# Sheet2.net
KiCad netlist of a schematic drawn in Altium Designer
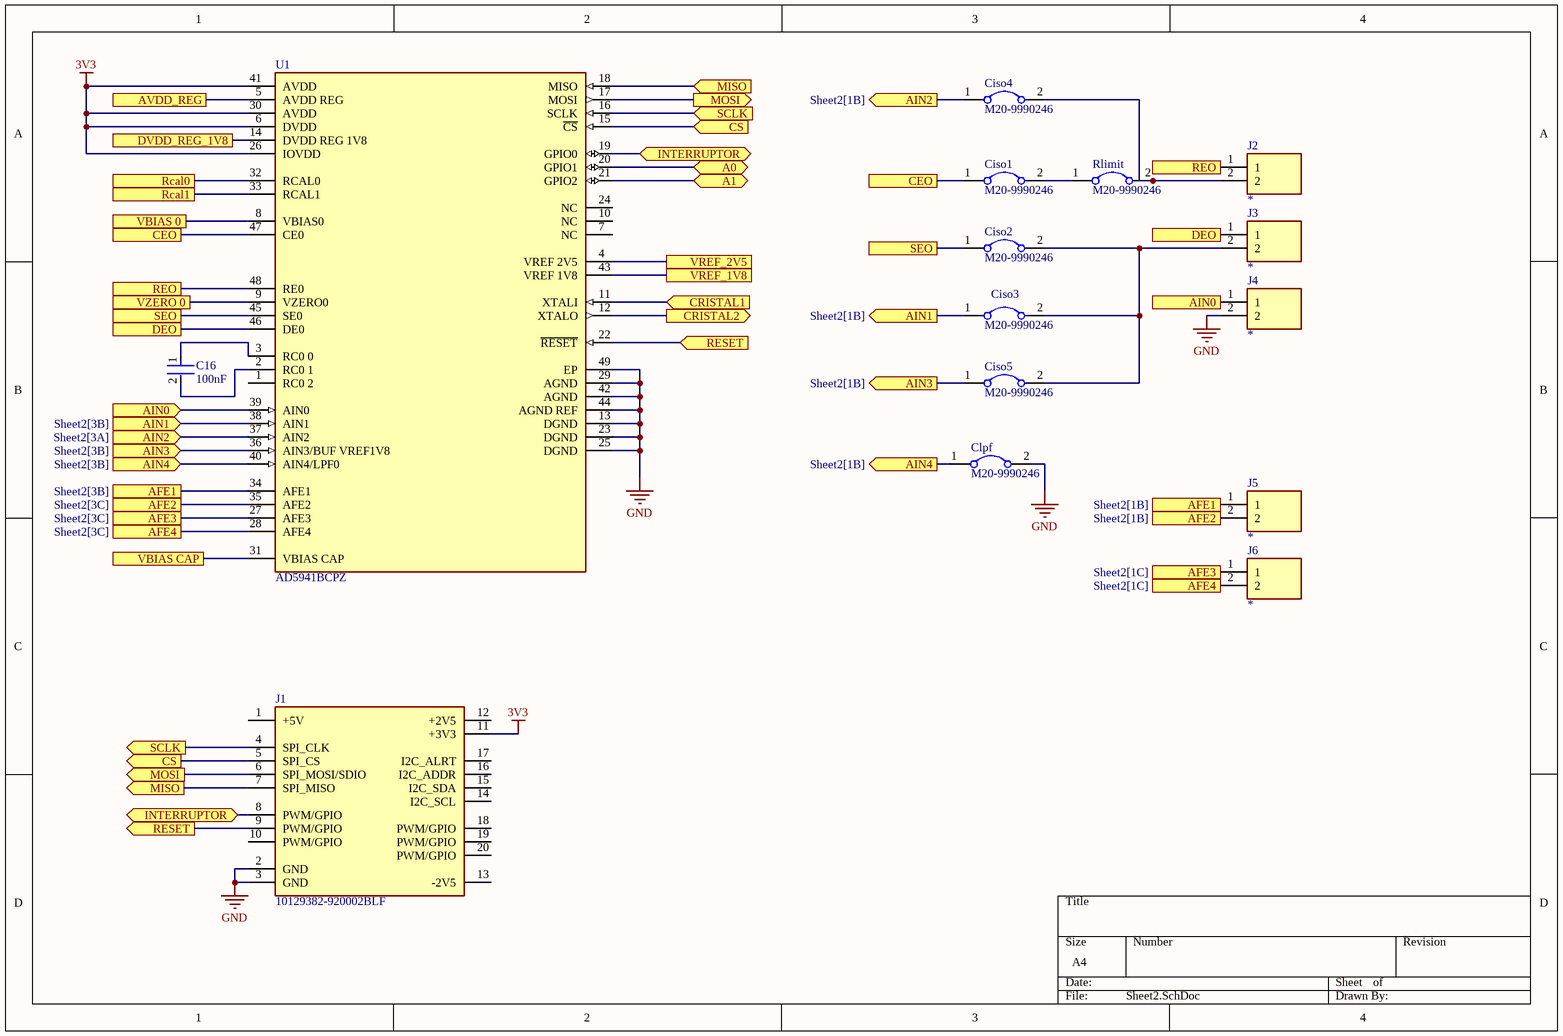
[diagram p0: Sheet2.SchDoc]

(export (version "E")
  (design (tool "Eeschema 10.0.6"))
  (components
    (comp (ref "C16")
      (value "100nF")
      (footprint "FP-GRM18-0_15-MFG")
      (description "CAP CER 10UF 10V X5R 0603")
      (fields
        (field (name "OCTOPART") "https://octopart.com/grm188r61a106ke69d-murata-22851381")
        (field (name "MANUFACTURER PART NUMBER") "GRM188R61A106KE69D")
      )
      (libsource (lib "Altium Content Vault") (part "11868f565c42a9108669ba33697ecf6"))
    )
    (comp (ref "Ciso1")
      (value "M20-9990246")
      (footprint "Male Header Socket 2-position")
      (description "Headers & Wire Housings M20 2 Position SIL VERTICAL PTH HEADER TIN")
      (libsource (lib "CEDRA_Connectors") (part "M20-9990246 (JUMPER)"))
    )
    (comp (ref "Ciso2")
      (value "M20-9990246")
      (footprint "Male Header Socket 2-position")
      (description "Headers & Wire Housings M20 2 Position SIL VERTICAL PTH HEADER TIN")
      (libsource (lib "CEDRA_Connectors") (part "M20-9990246 (JUMPER)"))
    )
    (comp (ref "Ciso3")
      (value "M20-9990246")
      (footprint "Male Header Socket 2-position")
      (description "Headers & Wire Housings M20 2 Position SIL VERTICAL PTH HEADER TIN")
      (libsource (lib "CEDRA_Connectors") (part "M20-9990246 (JUMPER)"))
    )
    (comp (ref "Ciso4")
      (value "M20-9990246")
      (footprint "Male Header Socket 2-position")
      (description "Headers & Wire Housings M20 2 Position SIL VERTICAL PTH HEADER TIN")
      (libsource (lib "CEDRA_Connectors") (part "M20-9990246 (JUMPER)"))
    )
    (comp (ref "Ciso5")
      (value "M20-9990246")
      (footprint "Male Header Socket 2-position")
      (description "Headers & Wire Housings M20 2 Position SIL VERTICAL PTH HEADER TIN")
      (libsource (lib "CEDRA_Connectors") (part "M20-9990246 (JUMPER)"))
    )
    (comp (ref "Clpf")
      (value "M20-9990246")
      (footprint "Male Header Socket 2-position")
      (description "Headers & Wire Housings M20 2 Position SIL VERTICAL PTH HEADER TIN")
      (libsource (lib "CEDRA_Connectors") (part "M20-9990246 (JUMPER)"))
    )
    (comp (ref "J1")
      (value "10129382-920002BLF")
      (footprint "Base Board Modular Connector (MALE)")
      (libsource (lib "CEDRA_Connectors") (part "Base Board Modular Connector (MALE)"))
    )
    (comp (ref "J2")
      (value "~")
      (footprint "Terminal Block 2-position")
      (fields (field (name "PARAMETER 1") "*"))
      (libsource (lib "CEDRA_Connectors") (part "TB0011-350-02BE"))
    )
    (comp (ref "J3")
      (value "~")
      (footprint "Terminal Block 2-position")
      (fields (field (name "PARAMETER 1") "*"))
      (libsource (lib "CEDRA_Connectors") (part "TB0011-350-02BE"))
    )
    (comp (ref "J4")
      (value "~")
      (footprint "Terminal Block 2-position")
      (fields (field (name "PARAMETER 1") "*"))
      (libsource (lib "CEDRA_Connectors") (part "TB0011-350-02BE"))
    )
    (comp (ref "J5")
      (value "~")
      (footprint "Terminal Block 2-position")
      (fields (field (name "PARAMETER 1") "*"))
      (libsource (lib "CEDRA_Connectors") (part "TB0011-350-02BE"))
    )
    (comp (ref "J6")
      (value "~")
      (footprint "Terminal Block 2-position")
      (fields (field (name "PARAMETER 1") "*"))
      (libsource (lib "CEDRA_Connectors") (part "TB0011-350-02BE"))
    )
    (comp (ref "Rlimit")
      (value "M20-9990246")
      (footprint "Male Header Socket 2-position")
      (description "Headers & Wire Housings M20 2 Position SIL VERTICAL PTH HEADER TIN")
      (libsource (lib "CEDRA_Connectors") (part "M20-9990246 (JUMPER)"))
    )
    (comp (ref "U1")
      (value "AD5941BCPZ")
      (footprint "FP-CP-48-4-IPC_A")
      (description "BIO-IMPEDANCE & ELECTROCHEMICAL")
      (libsource (lib "Altium Content Vault") (part "6a54f8959a82146fbd7e10af4c03d01"))
    )
  )
  (nets
    (net (code "1") (name "/A0") (class "Default")
      (node (ref "U1") (pin "20") (pinfunction "GPIO1_20") (pintype "bidirectional"))
    )
    (net (code "2") (name "/A1") (class "Default")
      (node (ref "U1") (pin "21") (pinfunction "GPIO2_21") (pintype "bidirectional"))
    )
    (net (code "3") (name "/AFE1") (class "Default")
      (node (ref "J5") (pin "1") (pinfunction "1_1") (pintype "passive"))
      (node (ref "U1") (pin "34") (pinfunction "AFE1_34") (pintype "passive"))
    )
    (net (code "4") (name "/AFE2") (class "Default")
      (node (ref "J5") (pin "2") (pinfunction "2_2") (pintype "passive"))
      (node (ref "U1") (pin "35") (pinfunction "AFE2_35") (pintype "passive"))
    )
    (net (code "5") (name "/AFE3") (class "Default")
      (node (ref "J6") (pin "1") (pinfunction "1_1") (pintype "passive"))
      (node (ref "U1") (pin "27") (pinfunction "AFE3_27") (pintype "passive"))
    )
    (net (code "6") (name "/AFE4") (class "Default")
      (node (ref "J6") (pin "2") (pinfunction "2_2") (pintype "passive"))
      (node (ref "U1") (pin "28") (pinfunction "AFE4_28") (pintype "passive"))
    )
    (net (code "7") (name "/AIN0") (class "Default")
      (node (ref "J4") (pin "1") (pinfunction "1_1") (pintype "passive"))
      (node (ref "U1") (pin "39") (pinfunction "AIN0_39") (pintype "input"))
    )
    (net (code "8") (name "/AIN1") (class "Default")
      (node (ref "Ciso3") (pin "1") (pinfunction "1_1") (pintype "passive"))
      (node (ref "U1") (pin "38") (pinfunction "AIN1_38") (pintype "input"))
    )
    (net (code "9") (name "/AIN2") (class "Default")
      (node (ref "Ciso4") (pin "1") (pinfunction "1_1") (pintype "passive"))
      (node (ref "U1") (pin "37") (pinfunction "AIN2_37") (pintype "input"))
    )
    (net (code "10") (name "/AIN3") (class "Default")
      (node (ref "Ciso5") (pin "1") (pinfunction "1_1") (pintype "passive"))
      (node (ref "U1") (pin "36") (pinfunction "AIN3/BUF_VREF1V8_36") (pintype "input"))
    )
    (net (code "11") (name "/AIN4") (class "Default")
      (node (ref "Clpf") (pin "1") (pinfunction "1_1") (pintype "passive"))
      (node (ref "U1") (pin "40") (pinfunction "AIN4/LPF0_40") (pintype "input"))
    )
    (net (code "12") (name "/AVDD_REG") (class "Default")
      (node (ref "U1") (pin "5") (pinfunction "AVDD_REG_5") (pintype "power_in"))
    )
    (net (code "13") (name "/CEO") (class "Default")
      (node (ref "Ciso1") (pin "1") (pinfunction "1_1") (pintype "passive"))
      (node (ref "U1") (pin "47") (pinfunction "CE0_47") (pintype "passive"))
    )
    (net (code "14") (name "/CRISTAL1") (class "Default")
      (node (ref "U1") (pin "11") (pinfunction "XTALI_11") (pintype "input"))
    )
    (net (code "15") (name "/CRISTAL2") (class "Default")
      (node (ref "U1") (pin "12") (pinfunction "XTALO_12") (pintype "output"))
    )
    (net (code "16") (name "/CS") (class "Default")
      (node (ref "J1") (pin "5") (pinfunction "SPI_CS_5") (pintype "passive"))
      (node (ref "U1") (pin "15") (pinfunction "~{CS}_15") (pintype "input"))
    )
    (net (code "17") (name "/DEO") (class "Default")
      (node (ref "J3") (pin "1") (pinfunction "1_1") (pintype "passive"))
      (node (ref "U1") (pin "46") (pinfunction "DE0_46") (pintype "passive"))
    )
    (net (code "18") (name "/DVDD_REG_1V8") (class "Default")
      (node (ref "U1") (pin "14") (pinfunction "DVDD_REG_1V8_14") (pintype "power_in"))
    )
    (net (code "19") (name "/INTERRUPTOR") (class "Default")
      (node (ref "J1") (pin "8") (pinfunction "PWM/GPIO_8") (pintype "passive"))
      (node (ref "U1") (pin "19") (pinfunction "GPIO0_19") (pintype "bidirectional"))
    )
    (net (code "20") (name "/MISO") (class "Default")
      (node (ref "J1") (pin "7") (pinfunction "SPI_MISO_7") (pintype "passive"))
      (node (ref "U1") (pin "18") (pinfunction "MISO_18") (pintype "input"))
    )
    (net (code "21") (name "/MOSI") (class "Default")
      (node (ref "J1") (pin "6") (pinfunction "SPI_MOSI/SDIO_6") (pintype "passive"))
      (node (ref "U1") (pin "17") (pinfunction "MOSI_17") (pintype "output"))
    )
    (net (code "22") (name "/REO") (class "Default")
      (node (ref "J2") (pin "1") (pinfunction "1_1") (pintype "passive"))
      (node (ref "U1") (pin "48") (pinfunction "RE0_48") (pintype "passive"))
    )
    (net (code "23") (name "/RESET") (class "Default")
      (node (ref "J1") (pin "9") (pinfunction "PWM/GPIO_9") (pintype "passive"))
      (node (ref "U1") (pin "22") (pinfunction "~{RESET}_22") (pintype "input"))
    )
    (net (code "24") (name "/Rcal0") (class "Default")
      (node (ref "U1") (pin "32") (pinfunction "RCAL0_32") (pintype "passive"))
    )
    (net (code "25") (name "/Rcal1") (class "Default")
      (node (ref "U1") (pin "33") (pinfunction "RCAL1_33") (pintype "passive"))
    )
    (net (code "26") (name "/SCLK") (class "Default")
      (node (ref "J1") (pin "4") (pinfunction "SPI_CLK_4") (pintype "passive"))
      (node (ref "U1") (pin "16") (pinfunction "SCLK_16") (pintype "input"))
    )
    (net (code "27") (name "/SEO") (class "Default")
      (node (ref "Ciso2") (pin "1") (pinfunction "1_1") (pintype "passive"))
      (node (ref "U1") (pin "45") (pinfunction "SE0_45") (pintype "passive"))
    )
    (net (code "28") (name "/VBIAS 0") (class "Default")
      (node (ref "U1") (pin "8") (pinfunction "VBIAS0_8") (pintype "passive"))
    )
    (net (code "29") (name "/VBIAS CAP") (class "Default")
      (node (ref "U1") (pin "31") (pinfunction "VBIAS_CAP_31") (pintype "power_in"))
    )
    (net (code "30") (name "/VREF_1V8") (class "Default")
      (node (ref "U1") (pin "43") (pinfunction "VREF_1V8_43") (pintype "power_in"))
    )
    (net (code "31") (name "/VREF_2V5") (class "Default")
      (node (ref "U1") (pin "4") (pinfunction "VREF_2V5_4") (pintype "power_in"))
    )
    (net (code "32") (name "/VZERO 0") (class "Default")
      (node (ref "U1") (pin "9") (pinfunction "VZERO0_9") (pintype "passive"))
    )
    (net (code "33") (name "3V3") (class "Default")
      (node (ref "J1") (pin "11") (pinfunction "+3V3_11") (pintype "passive"))
      (node (ref "U1") (pin "26") (pinfunction "IOVDD_26") (pintype "power_in"))
      (node (ref "U1") (pin "30") (pinfunction "AVDD_30") (pintype "power_in"))
      (node (ref "U1") (pin "41") (pinfunction "AVDD_41") (pintype "power_in"))
      (node (ref "U1") (pin "6") (pinfunction "DVDD_6") (pintype "power_in"))
    )
    (net (code "34") (name "GND") (class "Default")
      (node (ref "Clpf") (pin "2") (pinfunction "2_2") (pintype "passive"))
      (node (ref "J1") (pin "2") (pinfunction "GND_2") (pintype "passive"))
      (node (ref "J1") (pin "3") (pinfunction "GND_3") (pintype "passive"))
      (node (ref "J4") (pin "2") (pinfunction "2_2") (pintype "passive"))
      (node (ref "U1") (pin "13") (pinfunction "DGND_13") (pintype "power_in"))
      (node (ref "U1") (pin "23") (pinfunction "DGND_23") (pintype "power_in"))
      (node (ref "U1") (pin "25") (pinfunction "DGND_25") (pintype "power_in"))
      (node (ref "U1") (pin "29") (pinfunction "AGND_29") (pintype "power_in"))
      (node (ref "U1") (pin "42") (pinfunction "AGND_42") (pintype "power_in"))
      (node (ref "U1") (pin "44") (pinfunction "AGND_REF_44") (pintype "power_in"))
      (node (ref "U1") (pin "49") (pinfunction "EP_49") (pintype "passive"))
    )
    (net (code "35") (name "Net-(Ciso1-Pad2)") (class "Default")
      (node (ref "Ciso1") (pin "2") (pinfunction "2_2") (pintype "passive"))
      (node (ref "Rlimit") (pin "1") (pinfunction "1_1") (pintype "passive"))
    )
    (net (code "36") (name "Net-(Ciso2-Pad2)") (class "Default")
      (node (ref "Ciso2") (pin "2") (pinfunction "2_2") (pintype "passive"))
      (node (ref "Ciso3") (pin "2") (pinfunction "2_2") (pintype "passive"))
      (node (ref "Ciso5") (pin "2") (pinfunction "2_2") (pintype "passive"))
      (node (ref "J3") (pin "2") (pinfunction "2_2") (pintype "passive"))
    )
    (net (code "37") (name "Net-(Ciso4-Pad2)") (class "Default")
      (node (ref "Ciso4") (pin "2") (pinfunction "2_2") (pintype "passive"))
      (node (ref "J2") (pin "2") (pinfunction "2_2") (pintype "passive"))
      (node (ref "Rlimit") (pin "2") (pinfunction "2_2") (pintype "passive"))
    )
    (net (code "38") (name "Net-(U1-RC0_0)") (class "Default")
      (node (ref "C16") (pin "1") (pinfunction "1_1") (pintype "passive"))
      (node (ref "U1") (pin "3") (pinfunction "RC0_0_3") (pintype "passive"))
    )
    (net (code "39") (name "Net-(U1-RC0_1)") (class "Default")
      (node (ref "C16") (pin "2") (pinfunction "2_2") (pintype "passive"))
      (node (ref "U1") (pin "2") (pinfunction "RC0_1_2") (pintype "passive"))
    )
    (net (code "40") (name "unconnected-(J1-+2V5-Pad12)") (class "Default")
      (node (ref "J1") (pin "12") (pinfunction "+2V5_12") (pintype "passive"))
    )
    (net (code "41") (name "unconnected-(J1-+5V-Pad1)") (class "Default")
      (node (ref "J1") (pin "1") (pinfunction "+5V_1") (pintype "passive"))
    )
    (net (code "42") (name "unconnected-(J1--2V5-Pad13)") (class "Default")
      (node (ref "J1") (pin "13") (pinfunction "-2V5_13") (pintype "passive"))
    )
    (net (code "43") (name "unconnected-(J1-I2C_ADDR-Pad16)") (class "Default")
      (node (ref "J1") (pin "16") (pinfunction "I2C_ADDR_16") (pintype "passive"))
    )
    (net (code "44") (name "unconnected-(J1-I2C_ALRT-Pad17)") (class "Default")
      (node (ref "J1") (pin "17") (pinfunction "I2C_ALRT_17") (pintype "passive"))
    )
    (net (code "45") (name "unconnected-(J1-I2C_SCL-Pad14)") (class "Default")
      (node (ref "J1") (pin "14") (pinfunction "I2C_SCL_14") (pintype "passive"))
    )
    (net (code "46") (name "unconnected-(J1-I2C_SDA-Pad15)") (class "Default")
      (node (ref "J1") (pin "15") (pinfunction "I2C_SDA_15") (pintype "passive"))
    )
    (net (code "47") (name "unconnected-(J1-PWM{slash}GPIO-Pad10)") (class "Default")
      (node (ref "J1") (pin "10") (pinfunction "PWM/GPIO_10") (pintype "passive"))
    )
    (net (code "48") (name "unconnected-(J1-PWM{slash}GPIO-Pad18)") (class "Default")
      (node (ref "J1") (pin "18") (pinfunction "PWM/GPIO_18") (pintype "passive"))
    )
    (net (code "49") (name "unconnected-(J1-PWM{slash}GPIO-Pad19)") (class "Default")
      (node (ref "J1") (pin "19") (pinfunction "PWM/GPIO_19") (pintype "passive"))
    )
    (net (code "50") (name "unconnected-(J1-PWM{slash}GPIO-Pad20)") (class "Default")
      (node (ref "J1") (pin "20") (pinfunction "PWM/GPIO_20") (pintype "passive"))
    )
    (net (code "51") (name "unconnected-(U1-NC-Pad7)") (class "Default")
      (node (ref "U1") (pin "7") (pinfunction "NC_7") (pintype "passive"))
    )
    (net (code "52") (name "unconnected-(U1-NC-Pad10)") (class "Default")
      (node (ref "U1") (pin "10") (pinfunction "NC_10") (pintype "passive"))
    )
    (net (code "53") (name "unconnected-(U1-NC-Pad24)") (class "Default")
      (node (ref "U1") (pin "24") (pinfunction "NC_24") (pintype "passive"))
    )
    (net (code "54") (name "unconnected-(U1-RC0_2-Pad1)") (class "Default")
      (node (ref "U1") (pin "1") (pinfunction "RC0_2_1") (pintype "passive"))
    )
  )
)
